# C64_CHARSETSw_4k.net
KiCad netlist of a schematic drawn in EAGLE
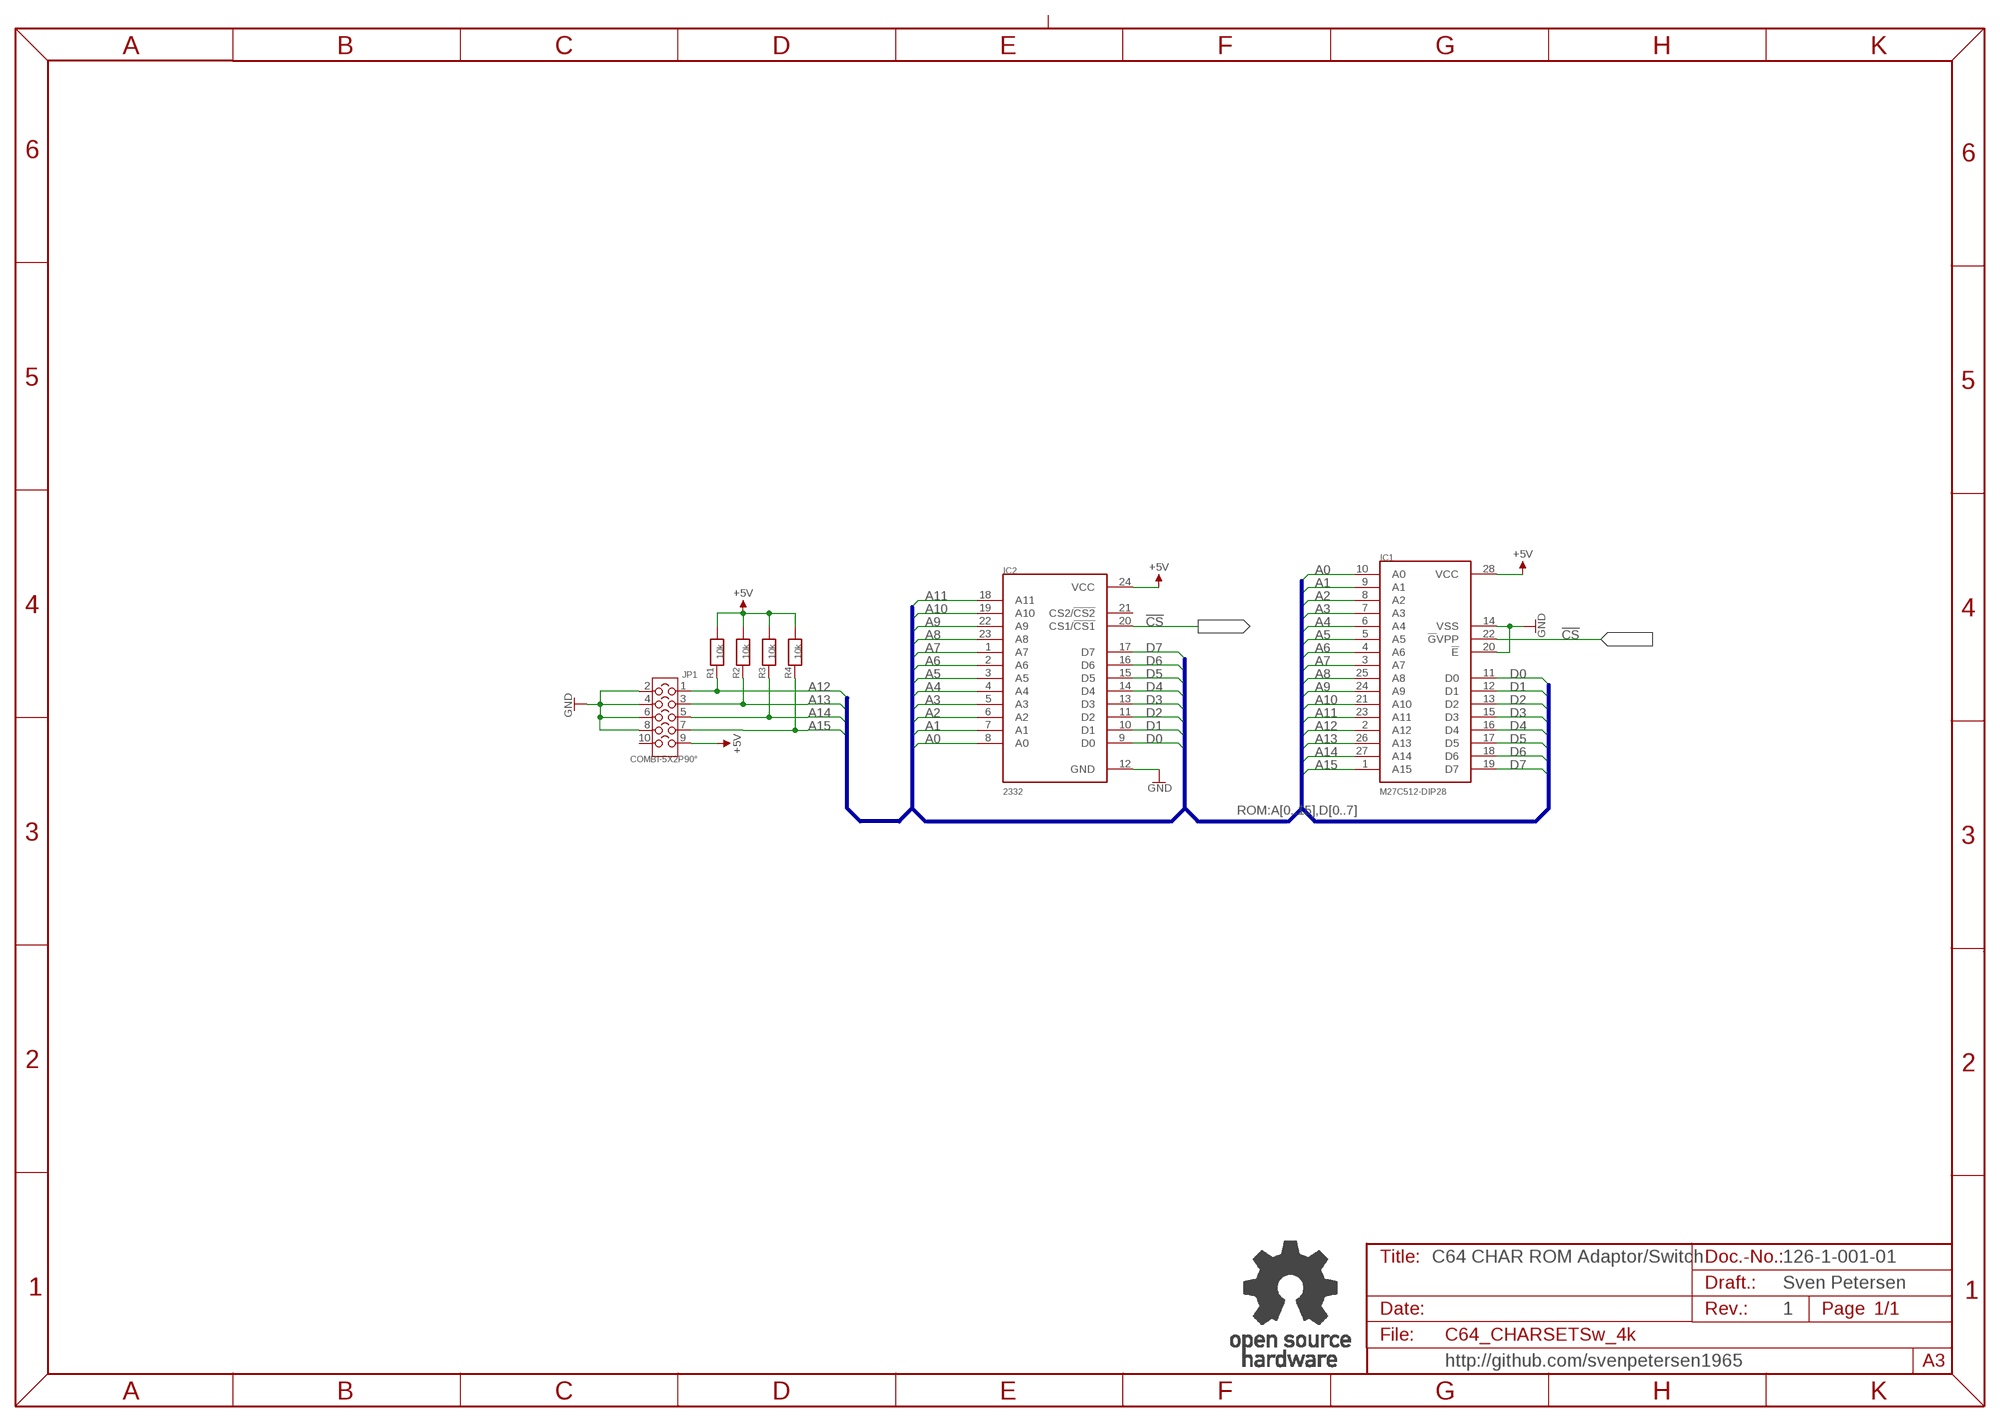
[diagram p0: schematic, sheet 1]

(export (version "E")
  (design (tool "Eeschema 10.0.6"))
  (components
    (comp (ref "IC1")
      (value "M27C512-DIP28")
      (footprint "eagle-import:DIL28-6")
      (libsource (lib "eagle-import") (part "M27C512-DIP28"))
    )
    (comp (ref "IC2")
      (value "2332")
      (footprint "eagle-import:DIL24_SOCKET")
      (libsource (lib "eagle-import") (part "2332"))
    )
    (comp (ref "JP1")
      (value "COMBI-5X2P90°")
      (footprint "eagle-import:COMBI-5X2-90")
      (libsource (lib "eagle-import") (part "COMBI-5X2P90°"))
    )
    (comp (ref "R1")
      (value "10k")
      (footprint "eagle-import:0805")
      (libsource (lib "eagle-import") (part "R-0805"))
    )
    (comp (ref "R2")
      (value "10k")
      (footprint "eagle-import:0805")
      (libsource (lib "eagle-import") (part "R-0805"))
    )
    (comp (ref "R3")
      (value "10k")
      (footprint "eagle-import:0805")
      (libsource (lib "eagle-import") (part "R-0805"))
    )
    (comp (ref "R4")
      (value "10k")
      (footprint "eagle-import:0805")
      (libsource (lib "eagle-import") (part "R-0805"))
    )
    (comp (ref "U$6")
      (value "OPEN_SOURCE_HW")
      (footprint "eagle-import:OPENHW")
      (libsource (lib "eagle-import") (part "OPEN_SOURCE_HW"))
    )
  )
  (nets
    (net (code "1") (name "+5V") (class "Default")
      (node (ref "IC1") (pin "28") (pinfunction "VCC_28") (pintype "power_in"))
      (node (ref "IC2") (pin "24") (pinfunction "VCC_24") (pintype "power_in"))
      (node (ref "JP1") (pin "9") (pinfunction "9_9") (pintype "bidirectional"))
      (node (ref "R1") (pin "2") (pinfunction "2_2") (pintype "passive"))
      (node (ref "R2") (pin "2") (pinfunction "2_2") (pintype "passive"))
      (node (ref "R3") (pin "2") (pinfunction "2_2") (pintype "passive"))
      (node (ref "R4") (pin "2") (pinfunction "2_2") (pintype "passive"))
    )
    (net (code "2") (name "/A0") (class "Default")
      (node (ref "IC1") (pin "10") (pinfunction "A0_10") (pintype "input"))
      (node (ref "IC2") (pin "8") (pinfunction "A0_8") (pintype "input"))
    )
    (net (code "3") (name "/A1") (class "Default")
      (node (ref "IC1") (pin "9") (pinfunction "A1_9") (pintype "input"))
      (node (ref "IC2") (pin "7") (pinfunction "A1_7") (pintype "input"))
    )
    (net (code "4") (name "/A2") (class "Default")
      (node (ref "IC1") (pin "8") (pinfunction "A2_8") (pintype "input"))
      (node (ref "IC2") (pin "6") (pinfunction "A2_6") (pintype "input"))
    )
    (net (code "5") (name "/A3") (class "Default")
      (node (ref "IC1") (pin "7") (pinfunction "A3_7") (pintype "input"))
      (node (ref "IC2") (pin "5") (pinfunction "A3_5") (pintype "input"))
    )
    (net (code "6") (name "/A4") (class "Default")
      (node (ref "IC1") (pin "6") (pinfunction "A4_6") (pintype "input"))
      (node (ref "IC2") (pin "4") (pinfunction "A4_4") (pintype "input"))
    )
    (net (code "7") (name "/A5") (class "Default")
      (node (ref "IC1") (pin "5") (pinfunction "A5_5") (pintype "input"))
      (node (ref "IC2") (pin "3") (pinfunction "A5_3") (pintype "input"))
    )
    (net (code "8") (name "/A6") (class "Default")
      (node (ref "IC1") (pin "4") (pinfunction "A6_4") (pintype "input"))
      (node (ref "IC2") (pin "2") (pinfunction "A6_2") (pintype "input"))
    )
    (net (code "9") (name "/A7") (class "Default")
      (node (ref "IC1") (pin "3") (pinfunction "A7_3") (pintype "input"))
      (node (ref "IC2") (pin "1") (pinfunction "A7_1") (pintype "input"))
    )
    (net (code "10") (name "/A8") (class "Default")
      (node (ref "IC1") (pin "25") (pinfunction "A8_25") (pintype "input"))
      (node (ref "IC2") (pin "23") (pinfunction "A8_23") (pintype "input"))
    )
    (net (code "11") (name "/A9") (class "Default")
      (node (ref "IC1") (pin "24") (pinfunction "A9_24") (pintype "input"))
      (node (ref "IC2") (pin "22") (pinfunction "A9_22") (pintype "input"))
    )
    (net (code "12") (name "/A10") (class "Default")
      (node (ref "IC1") (pin "21") (pinfunction "A10_21") (pintype "input"))
      (node (ref "IC2") (pin "19") (pinfunction "A10_19") (pintype "input"))
    )
    (net (code "13") (name "/A11") (class "Default")
      (node (ref "IC1") (pin "23") (pinfunction "A11_23") (pintype "input"))
      (node (ref "IC2") (pin "18") (pinfunction "A11_18") (pintype "input"))
    )
    (net (code "14") (name "/A12") (class "Default")
      (node (ref "IC1") (pin "2") (pinfunction "A12_2") (pintype "input"))
      (node (ref "JP1") (pin "1") (pinfunction "1_1") (pintype "bidirectional"))
      (node (ref "R1") (pin "1") (pinfunction "1_1") (pintype "passive"))
    )
    (net (code "15") (name "/A13") (class "Default")
      (node (ref "IC1") (pin "26") (pinfunction "A13_26") (pintype "input"))
      (node (ref "JP1") (pin "3") (pinfunction "3_3") (pintype "bidirectional"))
      (node (ref "R2") (pin "1") (pinfunction "1_1") (pintype "passive"))
    )
    (net (code "16") (name "/A14") (class "Default")
      (node (ref "IC1") (pin "27") (pinfunction "A14_27") (pintype "input"))
      (node (ref "JP1") (pin "5") (pinfunction "5_5") (pintype "bidirectional"))
      (node (ref "R3") (pin "1") (pinfunction "1_1") (pintype "passive"))
    )
    (net (code "17") (name "/A15") (class "Default")
      (node (ref "IC1") (pin "1") (pinfunction "A15_1") (pintype "input"))
      (node (ref "JP1") (pin "7") (pinfunction "7_7") (pintype "bidirectional"))
      (node (ref "R4") (pin "1") (pinfunction "1_1") (pintype "passive"))
    )
    (net (code "18") (name "/D0") (class "Default")
      (node (ref "IC1") (pin "11") (pinfunction "D0_11") (pintype "bidirectional"))
      (node (ref "IC2") (pin "9") (pinfunction "D0_9") (pintype "tri_state"))
    )
    (net (code "19") (name "/D1") (class "Default")
      (node (ref "IC1") (pin "12") (pinfunction "D1_12") (pintype "bidirectional"))
      (node (ref "IC2") (pin "10") (pinfunction "D1_10") (pintype "tri_state"))
    )
    (net (code "20") (name "/D2") (class "Default")
      (node (ref "IC1") (pin "13") (pinfunction "D2_13") (pintype "bidirectional"))
      (node (ref "IC2") (pin "11") (pinfunction "D2_11") (pintype "tri_state"))
    )
    (net (code "21") (name "/D3") (class "Default")
      (node (ref "IC1") (pin "15") (pinfunction "D3_15") (pintype "bidirectional"))
      (node (ref "IC2") (pin "13") (pinfunction "D3_13") (pintype "tri_state"))
    )
    (net (code "22") (name "/D4") (class "Default")
      (node (ref "IC1") (pin "16") (pinfunction "D4_16") (pintype "bidirectional"))
      (node (ref "IC2") (pin "14") (pinfunction "D4_14") (pintype "tri_state"))
    )
    (net (code "23") (name "/D5") (class "Default")
      (node (ref "IC1") (pin "17") (pinfunction "D5_17") (pintype "bidirectional"))
      (node (ref "IC2") (pin "15") (pinfunction "D5_15") (pintype "tri_state"))
    )
    (net (code "24") (name "/D6") (class "Default")
      (node (ref "IC1") (pin "18") (pinfunction "D6_18") (pintype "bidirectional"))
      (node (ref "IC2") (pin "16") (pinfunction "D6_16") (pintype "tri_state"))
    )
    (net (code "25") (name "/D7") (class "Default")
      (node (ref "IC1") (pin "19") (pinfunction "D7_19") (pintype "bidirectional"))
      (node (ref "IC2") (pin "17") (pinfunction "D7_17") (pintype "tri_state"))
    )
    (net (code "27") (name "/~{CS}") (class "Default")
      (node (ref "IC1") (pin "22") (pinfunction "~{G}VPP_22") (pintype "input"))
      (node (ref "IC2") (pin "20") (pinfunction "CS1/~{CS1}_20") (pintype "input"))
    )
    (net (code "28") (name "GND") (class "Default")
      (node (ref "IC1") (pin "14") (pinfunction "VSS_14") (pintype "power_in"))
      (node (ref "IC1") (pin "20") (pinfunction "~{E}_20") (pintype "input"))
      (node (ref "IC2") (pin "12") (pinfunction "GND_12") (pintype "power_in"))
      (node (ref "JP1") (pin "2") (pinfunction "2_2") (pintype "bidirectional"))
      (node (ref "JP1") (pin "4") (pinfunction "4_4") (pintype "bidirectional"))
      (node (ref "JP1") (pin "6") (pinfunction "6_6") (pintype "bidirectional"))
      (node (ref "JP1") (pin "8") (pinfunction "8_8") (pintype "bidirectional"))
    )
    (net (code "29") (name "unconnected-(IC2-CS2{slash}~{CS2}-Pad21)") (class "Default")
      (node (ref "IC2") (pin "21") (pinfunction "CS2/~{CS2}_21") (pintype "input"))
    )
    (net (code "30") (name "unconnected-(JP1-Pad10)") (class "Default")
      (node (ref "JP1") (pin "10") (pinfunction "10_10") (pintype "bidirectional"))
    )
  )
)
